# crown-B.net
KiCad netlist of a schematic drawn in EAGLE
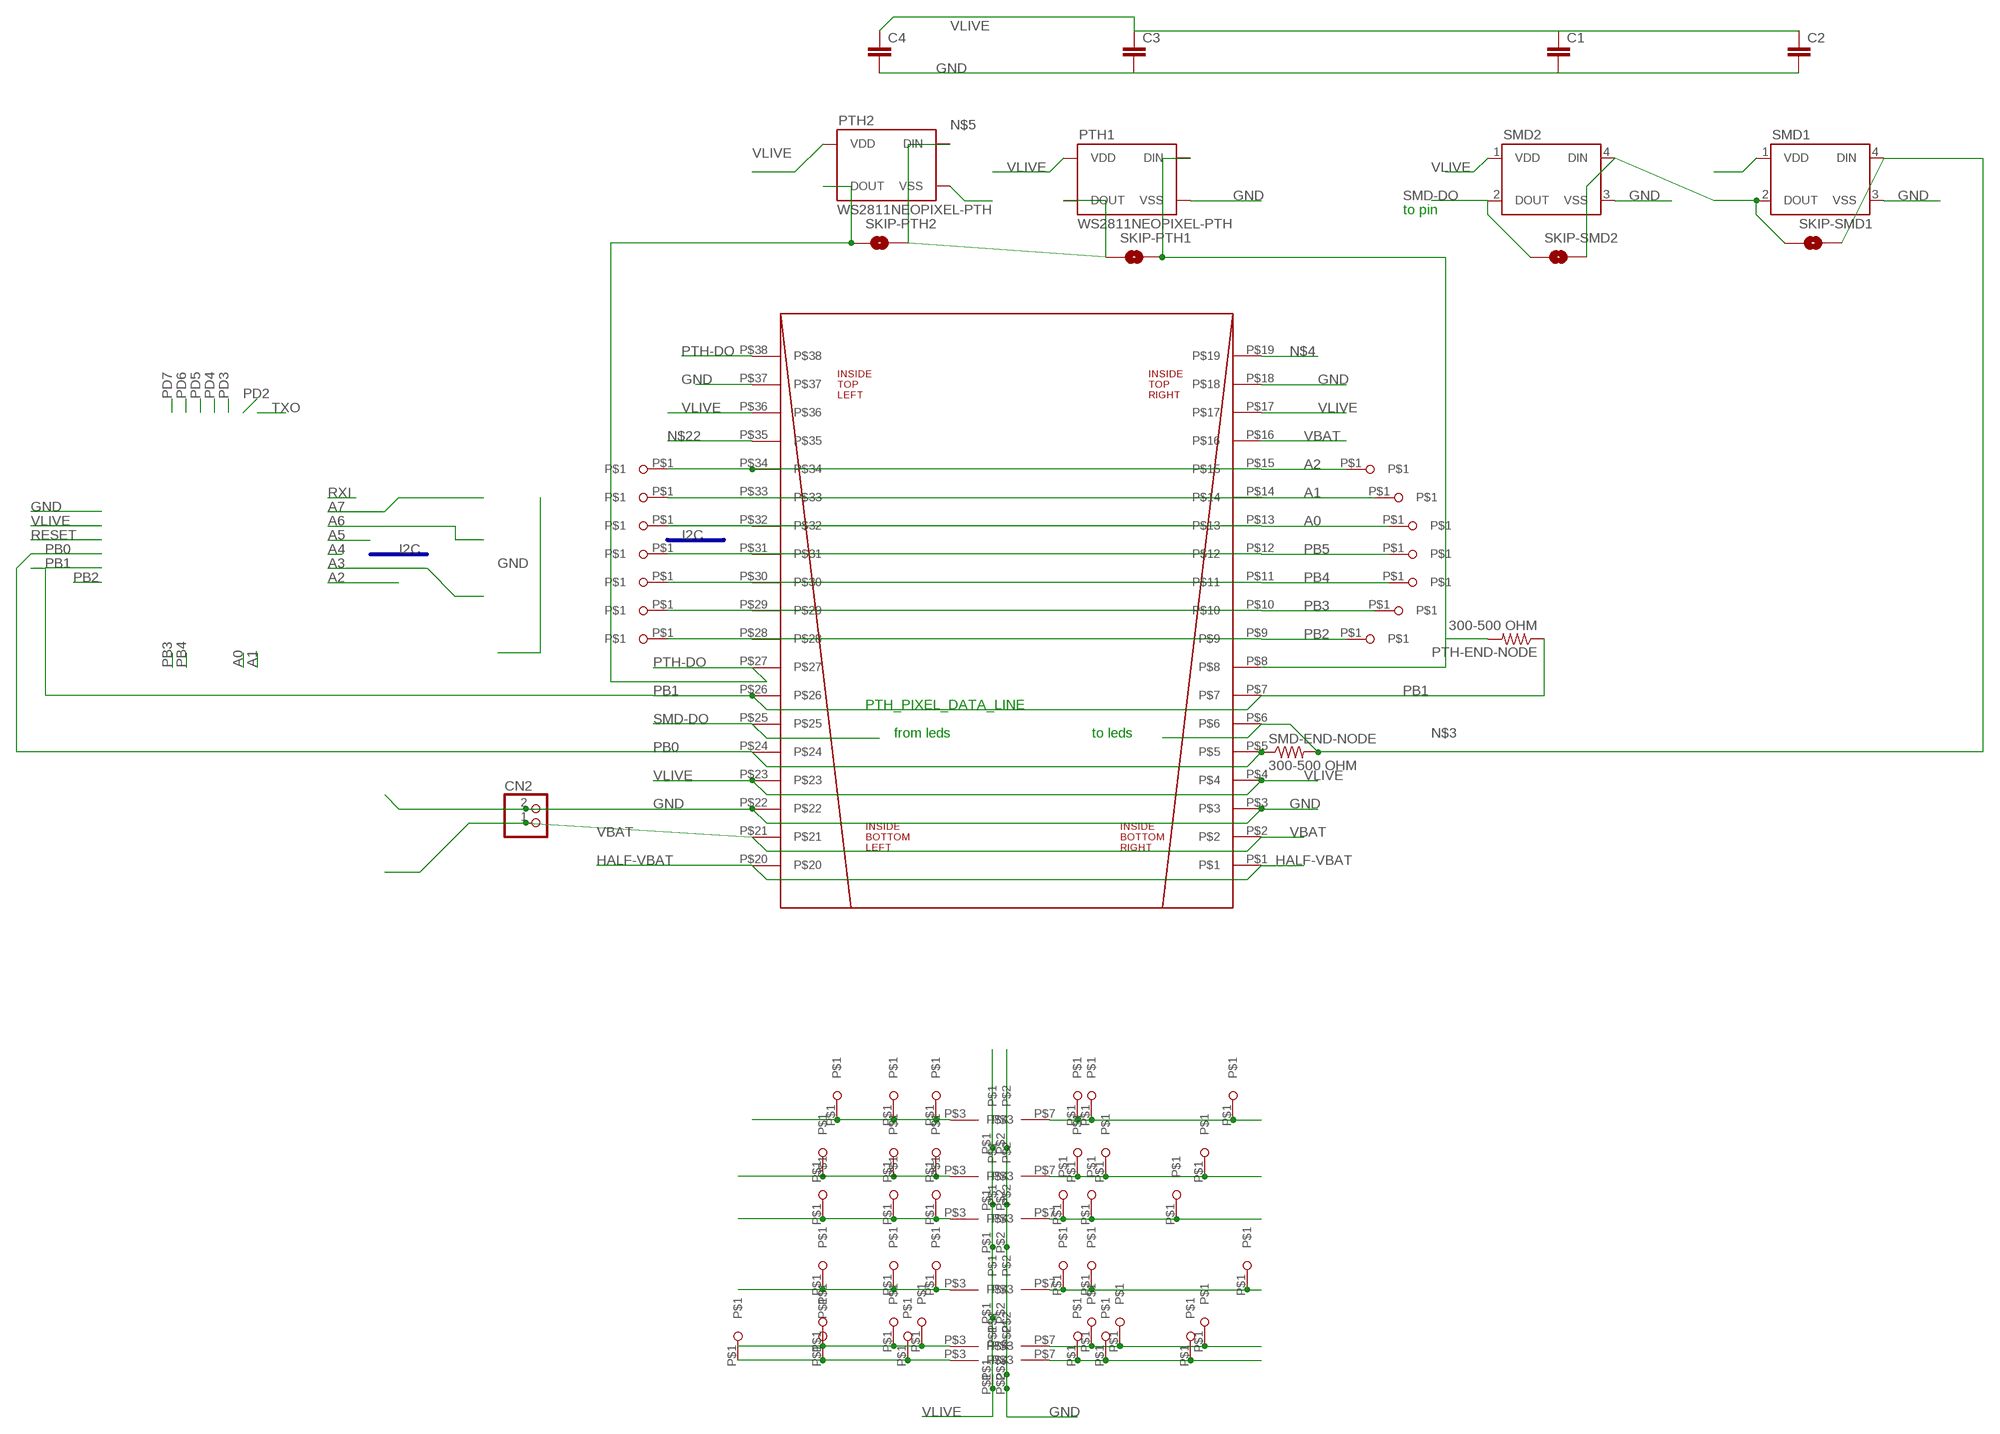
[diagram p0: schematic, sheet 1]

(export (version "E")
  (design (tool "Eeschema 10.0.6"))
  (components
    (comp (ref "C1")
      (value "CAP0805")
      (footprint "eagle-import:0805")
      (libsource (lib "eagle-import") (part "CAP0805"))
    )
    (comp (ref "C2")
      (value "CAP0805")
      (footprint "eagle-import:0805")
      (libsource (lib "eagle-import") (part "CAP0805"))
    )
    (comp (ref "C3")
      (value "CAP0805")
      (footprint "eagle-import:0805")
      (libsource (lib "eagle-import") (part "CAP0805"))
    )
    (comp (ref "C4")
      (value "CAP0805")
      (footprint "eagle-import:0805")
      (libsource (lib "eagle-import") (part "CAP0805"))
    )
    (comp (ref "CN2")
      (value "JST_2PIN-SMT-RA")
      (footprint "eagle-import:JST-PH-2-SMT-RA")
      (libsource (lib "eagle-import") (part "JST_2PIN-SMT-RA"))
    )
    (comp (ref "PTH-END-NODE")
      (value "300-500 OHM")
      (footprint "eagle-import:0805")
      (libsource (lib "eagle-import") (part "RESISTOR0805-RES"))
    )
    (comp (ref "PTH1")
      (value "WS2811NEOPIXEL-PTH")
      (footprint "eagle-import:WS2811-PTH-FLAT")
      (libsource (lib "eagle-import") (part "WS2811NEOPIXEL-PTH"))
    )
    (comp (ref "PTH2")
      (value "WS2811NEOPIXEL-PTH")
      (footprint "eagle-import:WS2811-PTH-FLAT")
      (libsource (lib "eagle-import") (part "WS2811NEOPIXEL-PTH"))
    )
    (comp (ref "SKIP-PTH1")
      (value "SOLDERJUMPERNC2")
      (footprint "eagle-import:SJ_2S-NOTRACE")
      (libsource (lib "eagle-import") (part "SOLDERJUMPERNC2"))
    )
    (comp (ref "SKIP-PTH2")
      (value "SOLDERJUMPERNC2")
      (footprint "eagle-import:SJ_2S-NOTRACE")
      (libsource (lib "eagle-import") (part "SOLDERJUMPERNC2"))
    )
    (comp (ref "SKIP-SMD1")
      (value "SOLDERJUMPERNC2")
      (footprint "eagle-import:SJ_2S-NOTRACE")
      (libsource (lib "eagle-import") (part "SOLDERJUMPERNC2"))
    )
    (comp (ref "SKIP-SMD2")
      (value "SOLDERJUMPERNC2")
      (footprint "eagle-import:SJ_2S-NOTRACE")
      (libsource (lib "eagle-import") (part "SOLDERJUMPERNC2"))
    )
    (comp (ref "SMD-END-NODE")
      (value "300-500 OHM")
      (footprint "eagle-import:0805")
      (libsource (lib "eagle-import") (part "RESISTOR0805-RES"))
    )
    (comp (ref "SMD1")
      (value "WS2812B")
      (footprint "eagle-import:WS2812B")
      (libsource (lib "eagle-import") (part "WS2812B"))
    )
    (comp (ref "SMD2")
      (value "WS2812B")
      (footprint "eagle-import:WS2812B")
      (libsource (lib "eagle-import") (part "WS2812B"))
    )
    (comp (ref "U$1")
      (value "SMD_BREADBOARD")
      (footprint "eagle-import:SMD_BREADBOARD_4X")
      (libsource (lib "eagle-import") (part "SMD_BREADBOARD"))
    )
    (comp (ref "U$2")
      (value "CROWNSTANDARD")
      (footprint "eagle-import:CROWN")
      (libsource (lib "eagle-import") (part "CROWNSTANDARD"))
    )
    (comp (ref "U$3")
      (value "SMD_BREADBOARD")
      (footprint "eagle-import:SMD_BREADBOARD_4X")
      (libsource (lib "eagle-import") (part "SMD_BREADBOARD"))
    )
    (comp (ref "U$4")
      (value "SMD_BREADBOARD")
      (footprint "eagle-import:SMD_BREADBOARD_4X")
      (libsource (lib "eagle-import") (part "SMD_BREADBOARD"))
    )
    (comp (ref "U$5")
      (value "SMD_BREADBOARD")
      (footprint "eagle-import:SMD_BREADBOARD_4X")
      (libsource (lib "eagle-import") (part "SMD_BREADBOARD"))
    )
    (comp (ref "U$6")
      (value "SMD_BREADBOARD")
      (footprint "eagle-import:SMD_BREADBOARD_4X")
      (libsource (lib "eagle-import") (part "SMD_BREADBOARD"))
    )
    (comp (ref "U$7")
      (value "SMD_BREADBOARD")
      (footprint "eagle-import:SMD_BREADBOARD_4X")
      (libsource (lib "eagle-import") (part "SMD_BREADBOARD"))
    )
    (comp (ref "U$10")
      (value "SMD_PAD")
      (footprint "eagle-import:SMD_BREADBOARD_PAD")
      (libsource (lib "eagle-import") (part "SMD_PAD"))
    )
    (comp (ref "U$11")
      (value "SMD_PAD")
      (footprint "eagle-import:SMD_BREADBOARD_PAD")
      (libsource (lib "eagle-import") (part "SMD_PAD"))
    )
    (comp (ref "U$12")
      (value "SMD_PAD")
      (footprint "eagle-import:SMD_BREADBOARD_PAD")
      (libsource (lib "eagle-import") (part "SMD_PAD"))
    )
    (comp (ref "U$13")
      (value "SMD_PAD")
      (footprint "eagle-import:SMD_BREADBOARD_PAD")
      (libsource (lib "eagle-import") (part "SMD_PAD"))
    )
    (comp (ref "U$14")
      (value "SMD_PAD")
      (footprint "eagle-import:SMD_BREADBOARD_PAD")
      (libsource (lib "eagle-import") (part "SMD_PAD"))
    )
    (comp (ref "U$15")
      (value "SMD_PAD")
      (footprint "eagle-import:SMD_BREADBOARD_PAD")
      (libsource (lib "eagle-import") (part "SMD_PAD"))
    )
    (comp (ref "U$16")
      (value "SMD_PAD")
      (footprint "eagle-import:SMD_BREADBOARD_PAD")
      (libsource (lib "eagle-import") (part "SMD_PAD"))
    )
    (comp (ref "U$17")
      (value "SMD_PAD")
      (footprint "eagle-import:SMD_BREADBOARD_PAD")
      (libsource (lib "eagle-import") (part "SMD_PAD"))
    )
    (comp (ref "U$22")
      (value "SMD_PAD")
      (footprint "eagle-import:SMD_BREADBOARD_PAD")
      (libsource (lib "eagle-import") (part "SMD_PAD"))
    )
    (comp (ref "U$23")
      (value "SMD_PAD")
      (footprint "eagle-import:SMD_BREADBOARD_PAD")
      (libsource (lib "eagle-import") (part "SMD_PAD"))
    )
    (comp (ref "U$24")
      (value "SMD_PAD")
      (footprint "eagle-import:SMD_BREADBOARD_PAD")
      (libsource (lib "eagle-import") (part "SMD_PAD"))
    )
    (comp (ref "U$25")
      (value "SMD_PAD")
      (footprint "eagle-import:SMD_BREADBOARD_PAD")
      (libsource (lib "eagle-import") (part "SMD_PAD"))
    )
    (comp (ref "U$26")
      (value "SMD_PAD")
      (footprint "eagle-import:SMD_BREADBOARD_PAD")
      (libsource (lib "eagle-import") (part "SMD_PAD"))
    )
    (comp (ref "U$27")
      (value "SMD_PAD")
      (footprint "eagle-import:SMD_BREADBOARD_PAD")
      (libsource (lib "eagle-import") (part "SMD_PAD"))
    )
    (comp (ref "U$28")
      (value "SMD_PAD")
      (footprint "eagle-import:SMD_BREADBOARD_PAD")
      (libsource (lib "eagle-import") (part "SMD_PAD"))
    )
    (comp (ref "U$29")
      (value "SMD_PAD")
      (footprint "eagle-import:SMD_BREADBOARD_PAD")
      (libsource (lib "eagle-import") (part "SMD_PAD"))
    )
    (comp (ref "U$34")
      (value "SMD_PAD")
      (footprint "eagle-import:SMD_BREADBOARD_PAD")
      (libsource (lib "eagle-import") (part "SMD_PAD"))
    )
    (comp (ref "U$35")
      (value "SMD_PAD")
      (footprint "eagle-import:SMD_BREADBOARD_PAD")
      (libsource (lib "eagle-import") (part "SMD_PAD"))
    )
    (comp (ref "U$36")
      (value "SMD_PAD")
      (footprint "eagle-import:SMD_BREADBOARD_PAD")
      (libsource (lib "eagle-import") (part "SMD_PAD"))
    )
    (comp (ref "U$37")
      (value "SMD_PAD")
      (footprint "eagle-import:SMD_BREADBOARD_PAD")
      (libsource (lib "eagle-import") (part "SMD_PAD"))
    )
    (comp (ref "U$38")
      (value "SMD_PAD")
      (footprint "eagle-import:SMD_BREADBOARD_PAD")
      (libsource (lib "eagle-import") (part "SMD_PAD"))
    )
    (comp (ref "U$39")
      (value "SMD_PAD")
      (footprint "eagle-import:SMD_BREADBOARD_PAD")
      (libsource (lib "eagle-import") (part "SMD_PAD"))
    )
    (comp (ref "U$40")
      (value "SMD_PAD")
      (footprint "eagle-import:SMD_BREADBOARD_PAD")
      (libsource (lib "eagle-import") (part "SMD_PAD"))
    )
    (comp (ref "U$41")
      (value "SMD_PAD")
      (footprint "eagle-import:SMD_BREADBOARD_PAD")
      (libsource (lib "eagle-import") (part "SMD_PAD"))
    )
    (comp (ref "U$42")
      (value "SMD_PAD")
      (footprint "eagle-import:SMD_BREADBOARD_PAD")
      (libsource (lib "eagle-import") (part "SMD_PAD"))
    )
    (comp (ref "U$43")
      (value "SMD_PAD")
      (footprint "eagle-import:SMD_BREADBOARD_PAD")
      (libsource (lib "eagle-import") (part "SMD_PAD"))
    )
    (comp (ref "U$44")
      (value "SMD_PAD")
      (footprint "eagle-import:SMD_BREADBOARD_PAD")
      (libsource (lib "eagle-import") (part "SMD_PAD"))
    )
    (comp (ref "U$45")
      (value "SMD_PAD")
      (footprint "eagle-import:SMD_BREADBOARD_PAD")
      (libsource (lib "eagle-import") (part "SMD_PAD"))
    )
    (comp (ref "U$46")
      (value "SMD_PAD")
      (footprint "eagle-import:SMD_BREADBOARD_PAD")
      (libsource (lib "eagle-import") (part "SMD_PAD"))
    )
    (comp (ref "U$47")
      (value "SMD_PAD")
      (footprint "eagle-import:SMD_BREADBOARD_PAD")
      (libsource (lib "eagle-import") (part "SMD_PAD"))
    )
    (comp (ref "U$48")
      (value "SMD_PAD")
      (footprint "eagle-import:SMD_BREADBOARD_PAD")
      (libsource (lib "eagle-import") (part "SMD_PAD"))
    )
    (comp (ref "U$49")
      (value "SMD_PAD")
      (footprint "eagle-import:SMD_BREADBOARD_PAD")
      (libsource (lib "eagle-import") (part "SMD_PAD"))
    )
    (comp (ref "U$50")
      (value "SMD_PAD")
      (footprint "eagle-import:SMD_BREADBOARD_PAD")
      (libsource (lib "eagle-import") (part "SMD_PAD"))
    )
    (comp (ref "U$51")
      (value "SMD_PAD")
      (footprint "eagle-import:SMD_BREADBOARD_PAD")
      (libsource (lib "eagle-import") (part "SMD_PAD"))
    )
    (comp (ref "U$52")
      (value "SMD_PAD")
      (footprint "eagle-import:SMD_BREADBOARD_PAD")
      (libsource (lib "eagle-import") (part "SMD_PAD"))
    )
    (comp (ref "U$53")
      (value "SMD_PAD")
      (footprint "eagle-import:SMD_BREADBOARD_PAD")
      (libsource (lib "eagle-import") (part "SMD_PAD"))
    )
    (comp (ref "U$54")
      (value "SMD_PAD")
      (footprint "eagle-import:SMD_BREADBOARD_PAD")
      (libsource (lib "eagle-import") (part "SMD_PAD"))
    )
    (comp (ref "U$55")
      (value "SMD_PAD")
      (footprint "eagle-import:SMD_BREADBOARD_PAD")
      (libsource (lib "eagle-import") (part "SMD_PAD"))
    )
    (comp (ref "U$56")
      (value "SMD_PAD")
      (footprint "eagle-import:SMD_BREADBOARD_PAD")
      (libsource (lib "eagle-import") (part "SMD_PAD"))
    )
    (comp (ref "U$57")
      (value "SMD_PAD")
      (footprint "eagle-import:SMD_BREADBOARD_PAD")
      (libsource (lib "eagle-import") (part "SMD_PAD"))
    )
    (comp (ref "U$58")
      (value "SMD_PAD")
      (footprint "eagle-import:SMD_BREADBOARD_PAD")
      (libsource (lib "eagle-import") (part "SMD_PAD"))
    )
    (comp (ref "U$59")
      (value "SMD_PAD")
      (footprint "eagle-import:SMD_BREADBOARD_PAD")
      (libsource (lib "eagle-import") (part "SMD_PAD"))
    )
    (comp (ref "U$62")
      (value "SMD_PAD")
      (footprint "eagle-import:SMD_BREADBOARD_PAD")
      (libsource (lib "eagle-import") (part "SMD_PAD"))
    )
    (comp (ref "U$63")
      (value "SMD_PAD")
      (footprint "eagle-import:SMD_BREADBOARD_PAD")
      (libsource (lib "eagle-import") (part "SMD_PAD"))
    )
    (comp (ref "U$64")
      (value "SMD_PAD")
      (footprint "eagle-import:SMD_BREADBOARD_PAD")
      (libsource (lib "eagle-import") (part "SMD_PAD"))
    )
    (comp (ref "U$65")
      (value "SMD_PAD")
      (footprint "eagle-import:SMD_BREADBOARD_PAD")
      (libsource (lib "eagle-import") (part "SMD_PAD"))
    )
    (comp (ref "U$68")
      (value "SMD_PAD")
      (footprint "eagle-import:SMD_BREADBOARD_PAD")
      (libsource (lib "eagle-import") (part "SMD_PAD"))
    )
    (comp (ref "U$69")
      (value "SMD_PAD")
      (footprint "eagle-import:SMD_BREADBOARD_PAD")
      (libsource (lib "eagle-import") (part "SMD_PAD"))
    )
    (comp (ref "U$70")
      (value "SMD_PAD")
      (footprint "eagle-import:SMD_BREADBOARD_PAD")
      (libsource (lib "eagle-import") (part "SMD_PAD"))
    )
    (comp (ref "U$71")
      (value "SMD_PAD")
      (footprint "eagle-import:SMD_BREADBOARD_PAD")
      (libsource (lib "eagle-import") (part "SMD_PAD"))
    )
  )
  (nets
    (net (code "2") (name "/A0") (class "Default")
      (node (ref "U$2") (pin "P$13") (pinfunction "P$13_P$13") (pintype "bidirectional"))
      (node (ref "U$2") (pin "P$32") (pinfunction "P$32_P$32") (pintype "bidirectional"))
      (node (ref "U$44") (pin "P$1") (pinfunction "P$1_P$1") (pintype "bidirectional"))
      (node (ref "U$55") (pin "P$1") (pinfunction "P$1_P$1") (pintype "bidirectional"))
    )
    (net (code "3") (name "/A1") (class "Default")
      (node (ref "U$2") (pin "P$14") (pinfunction "P$14_P$14") (pintype "bidirectional"))
      (node (ref "U$2") (pin "P$33") (pinfunction "P$33_P$33") (pintype "bidirectional"))
      (node (ref "U$43") (pin "P$1") (pinfunction "P$1_P$1") (pintype "bidirectional"))
      (node (ref "U$56") (pin "P$1") (pinfunction "P$1_P$1") (pintype "bidirectional"))
    )
    (net (code "4") (name "/A2") (class "Default")
      (node (ref "U$2") (pin "P$15") (pinfunction "P$15_P$15") (pintype "bidirectional"))
      (node (ref "U$2") (pin "P$34") (pinfunction "P$34_P$34") (pintype "bidirectional"))
      (node (ref "U$42") (pin "P$1") (pinfunction "P$1_P$1") (pintype "bidirectional"))
      (node (ref "U$58") (pin "P$1") (pinfunction "P$1_P$1") (pintype "bidirectional"))
    )
    (net (code "10") (name "/GND") (class "Default")
      (node (ref "C1") (pin "2") (pinfunction "2_2") (pintype "passive"))
      (node (ref "C2") (pin "2") (pinfunction "2_2") (pintype "passive"))
      (node (ref "C3") (pin "2") (pinfunction "2_2") (pintype "passive"))
      (node (ref "C4") (pin "2") (pinfunction "2_2") (pintype "passive"))
      (node (ref "CN2") (pin "2") (pinfunction "1_2") (pintype "passive"))
      (node (ref "PTH1") (pin "P$2") (pinfunction "VSS_P$2") (pintype "power_in"))
      (node (ref "PTH1") (pin "P$6") (pinfunction "VSS_P$6") (pintype "power_in"))
      (node (ref "PTH2") (pin "P$2") (pinfunction "VSS_P$2") (pintype "power_in"))
      (node (ref "PTH2") (pin "P$6") (pinfunction "VSS_P$6") (pintype "power_in"))
      (node (ref "SMD1") (pin "3") (pinfunction "VSS_3") (pintype "power_in"))
      (node (ref "SMD2") (pin "3") (pinfunction "VSS_3") (pintype "power_in"))
      (node (ref "U$1") (pin "P$2") (pinfunction "P$2_P$2") (pintype "bidirectional"))
      (node (ref "U$2") (pin "P$18") (pinfunction "P$18_P$18") (pintype "bidirectional"))
      (node (ref "U$2") (pin "P$22") (pinfunction "P$22_P$22") (pintype "bidirectional"))
      (node (ref "U$2") (pin "P$3") (pinfunction "P$3_P$3") (pintype "bidirectional"))
      (node (ref "U$2") (pin "P$37") (pinfunction "P$37_P$37") (pintype "bidirectional"))
      (node (ref "U$3") (pin "P$2") (pinfunction "P$2_P$2") (pintype "bidirectional"))
      (node (ref "U$4") (pin "P$2") (pinfunction "P$2_P$2") (pintype "bidirectional"))
      (node (ref "U$5") (pin "P$2") (pinfunction "P$2_P$2") (pintype "bidirectional"))
      (node (ref "U$6") (pin "P$2") (pinfunction "P$2_P$2") (pintype "bidirectional"))
      (node (ref "U$7") (pin "P$2") (pinfunction "P$2_P$2") (pintype "bidirectional"))
    )
    (net (code "11") (name "/HALF-VBAT") (class "Default")
      (node (ref "U$2") (pin "P$1") (pinfunction "P$1_P$1") (pintype "bidirectional"))
      (node (ref "U$2") (pin "P$20") (pinfunction "P$20_P$20") (pintype "bidirectional"))
    )
    (net (code "12") (name "/N$3") (class "Default")
      (node (ref "SKIP-SMD1") (pin "2") (pinfunction "2_2") (pintype "passive"))
      (node (ref "SMD-END-NODE") (pin "2") (pinfunction "2_2") (pintype "passive"))
      (node (ref "SMD1") (pin "4") (pinfunction "DIN_4") (pintype "input"))
      (node (ref "U$2") (pin "P$6") (pinfunction "P$6_P$6") (pintype "bidirectional"))
    )
    (net (code "13") (name "/N$4") (class "Default")
      (node (ref "PTH-END-NODE") (pin "2") (pinfunction "2_2") (pintype "passive"))
      (node (ref "PTH1") (pin "P$4") (pinfunction "DIN_P$4") (pintype "input"))
      (node (ref "PTH1") (pin "P$8") (pinfunction "DIN_P$8") (pintype "input"))
      (node (ref "SKIP-PTH1") (pin "2") (pinfunction "2_2") (pintype "passive"))
      (node (ref "U$2") (pin "P$19") (pinfunction "P$19_P$19") (pintype "bidirectional"))
      (node (ref "U$2") (pin "P$8") (pinfunction "P$8_P$8") (pintype "bidirectional"))
    )
    (net (code "14") (name "/N$5") (class "Default")
      (node (ref "PTH1") (pin "P$1") (pinfunction "DOUT_P$1") (pintype "output"))
      (node (ref "PTH1") (pin "P$5") (pinfunction "DOUT_P$5") (pintype "output"))
      (node (ref "PTH2") (pin "P$4") (pinfunction "DIN_P$4") (pintype "input"))
      (node (ref "PTH2") (pin "P$8") (pinfunction "DIN_P$8") (pintype "input"))
      (node (ref "SKIP-PTH1") (pin "1") (pinfunction "1_1") (pintype "passive"))
      (node (ref "SKIP-PTH2") (pin "2") (pinfunction "2_2") (pintype "passive"))
    )
    (net (code "15") (name "/N$22") (class "Default")
      (node (ref "U$2") (pin "P$35") (pinfunction "P$35_P$35") (pintype "bidirectional"))
    )
    (net (code "16") (name "/PB0") (class "Default")
      (node (ref "SMD-END-NODE") (pin "1") (pinfunction "1_1") (pintype "passive"))
      (node (ref "U$2") (pin "P$24") (pinfunction "P$24_P$24") (pintype "bidirectional"))
      (node (ref "U$2") (pin "P$5") (pinfunction "P$5_P$5") (pintype "bidirectional"))
    )
    (net (code "17") (name "/PB1") (class "Default")
      (node (ref "PTH-END-NODE") (pin "1") (pinfunction "1_1") (pintype "passive"))
      (node (ref "U$2") (pin "P$26") (pinfunction "P$26_P$26") (pintype "bidirectional"))
      (node (ref "U$2") (pin "P$7") (pinfunction "P$7_P$7") (pintype "bidirectional"))
    )
    (net (code "18") (name "/PB2") (class "Default")
      (node (ref "U$2") (pin "P$28") (pinfunction "P$28_P$28") (pintype "bidirectional"))
      (node (ref "U$2") (pin "P$9") (pinfunction "P$9_P$9") (pintype "bidirectional"))
      (node (ref "U$48") (pin "P$1") (pinfunction "P$1_P$1") (pintype "bidirectional"))
      (node (ref "U$51") (pin "P$1") (pinfunction "P$1_P$1") (pintype "bidirectional"))
    )
    (net (code "19") (name "/PB3") (class "Default")
      (node (ref "U$2") (pin "P$10") (pinfunction "P$10_P$10") (pintype "bidirectional"))
      (node (ref "U$2") (pin "P$29") (pinfunction "P$29_P$29") (pintype "bidirectional"))
      (node (ref "U$47") (pin "P$1") (pinfunction "P$1_P$1") (pintype "bidirectional"))
      (node (ref "U$52") (pin "P$1") (pinfunction "P$1_P$1") (pintype "bidirectional"))
    )
    (net (code "20") (name "/PB4") (class "Default")
      (node (ref "U$2") (pin "P$11") (pinfunction "P$11_P$11") (pintype "bidirectional"))
      (node (ref "U$2") (pin "P$30") (pinfunction "P$30_P$30") (pintype "bidirectional"))
      (node (ref "U$46") (pin "P$1") (pinfunction "P$1_P$1") (pintype "bidirectional"))
      (node (ref "U$53") (pin "P$1") (pinfunction "P$1_P$1") (pintype "bidirectional"))
    )
    (net (code "21") (name "/PB5") (class "Default")
      (node (ref "U$2") (pin "P$12") (pinfunction "P$12_P$12") (pintype "bidirectional"))
      (node (ref "U$2") (pin "P$31") (pinfunction "P$31_P$31") (pintype "bidirectional"))
      (node (ref "U$45") (pin "P$1") (pinfunction "P$1_P$1") (pintype "bidirectional"))
      (node (ref "U$54") (pin "P$1") (pinfunction "P$1_P$1") (pintype "bidirectional"))
    )
    (net (code "28") (name "/PTH-DO") (class "Default")
      (node (ref "PTH2") (pin "P$1") (pinfunction "DOUT_P$1") (pintype "output"))
      (node (ref "PTH2") (pin "P$5") (pinfunction "DOUT_P$5") (pintype "output"))
      (node (ref "SKIP-PTH2") (pin "1") (pinfunction "1_1") (pintype "passive"))
      (node (ref "U$2") (pin "P$27") (pinfunction "P$27_P$27") (pintype "bidirectional"))
      (node (ref "U$2") (pin "P$38") (pinfunction "P$38_P$38") (pintype "bidirectional"))
    )
    (net (code "31") (name "/SMD-DO") (class "Default")
      (node (ref "SKIP-SMD2") (pin "1") (pinfunction "1_1") (pintype "passive"))
      (node (ref "SMD2") (pin "2") (pinfunction "DOUT_2") (pintype "output"))
      (node (ref "U$2") (pin "P$25") (pinfunction "P$25_P$25") (pintype "bidirectional"))
    )
    (net (code "33") (name "/VBAT") (class "Default")
      (node (ref "CN2") (pin "1") (pinfunction "2_1") (pintype "passive"))
      (node (ref "U$2") (pin "P$16") (pinfunction "P$16_P$16") (pintype "bidirectional"))
      (node (ref "U$2") (pin "P$2") (pinfunction "P$2_P$2") (pintype "bidirectional"))
      (node (ref "U$2") (pin "P$21") (pinfunction "P$21_P$21") (pintype "bidirectional"))
    )
    (net (code "34") (name "/VLIVE") (class "Default")
      (node (ref "C1") (pin "1") (pinfunction "1_1") (pintype "passive"))
      (node (ref "C2") (pin "1") (pinfunction "1_1") (pintype "passive"))
      (node (ref "C3") (pin "1") (pinfunction "1_1") (pintype "passive"))
      (node (ref "C4") (pin "1") (pinfunction "1_1") (pintype "passive"))
      (node (ref "PTH1") (pin "P$3") (pinfunction "VDD_P$3") (pintype "power_in"))
      (node (ref "PTH1") (pin "P$7") (pinfunction "VDD_P$7") (pintype "power_in"))
      (node (ref "PTH2") (pin "P$3") (pinfunction "VDD_P$3") (pintype "power_in"))
      (node (ref "PTH2") (pin "P$7") (pinfunction "VDD_P$7") (pintype "power_in"))
      (node (ref "SMD1") (pin "1") (pinfunction "VDD_1") (pintype "power_in"))
      (node (ref "SMD2") (pin "1") (pinfunction "VDD_1") (pintype "power_in"))
      (node (ref "U$1") (pin "P$1") (pinfunction "P$1_P$1") (pintype "bidirectional"))
      (node (ref "U$2") (pin "P$17") (pinfunction "P$17_P$17") (pintype "bidirectional"))
      (node (ref "U$2") (pin "P$23") (pinfunction "P$23_P$23") (pintype "bidirectional"))
      (node (ref "U$2") (pin "P$36") (pinfunction "P$36_P$36") (pintype "bidirectional"))
      (node (ref "U$2") (pin "P$4") (pinfunction "P$4_P$4") (pintype "bidirectional"))
      (node (ref "U$3") (pin "P$1") (pinfunction "P$1_P$1") (pintype "bidirectional"))
      (node (ref "U$4") (pin "P$1") (pinfunction "P$1_P$1") (pintype "bidirectional"))
      (node (ref "U$5") (pin "P$1") (pinfunction "P$1_P$1") (pintype "bidirectional"))
      (node (ref "U$6") (pin "P$1") (pinfunction "P$1_P$1") (pintype "bidirectional"))
      (node (ref "U$7") (pin "P$1") (pinfunction "P$1_P$1") (pintype "bidirectional"))
    )
    (net (code "36") (name "Net-(SMD1-DOUT)") (class "Default")
      (node (ref "SKIP-SMD1") (pin "1") (pinfunction "1_1") (pintype "passive"))
      (node (ref "SKIP-SMD2") (pin "2") (pinfunction "2_2") (pintype "passive"))
      (node (ref "SMD1") (pin "2") (pinfunction "DOUT_2") (pintype "output"))
      (node (ref "SMD2") (pin "4") (pinfunction "DIN_4") (pintype "input"))
    )
    (net (code "37") (name "Net-(U$1-P$4)") (class "Default")
      (node (ref "U$1") (pin "P$7") (pinfunction "P$4_P$7") (pintype "bidirectional"))
      (node (ref "U$26") (pin "P$1") (pinfunction "P$1_P$1") (pintype "bidirectional"))
      (node (ref "U$27") (pin "P$1") (pinfunction "P$1_P$1") (pintype "bidirectional"))
      (node (ref "U$64") (pin "P$1") (pinfunction "P$1_P$1") (pintype "bidirectional"))
    )
    (net (code "38") (name "Net-(U$1-PadP$3)") (class "Default")
      (node (ref "U$1") (pin "P$3") (pinfunction "P$3_P$3") (pintype "bidirectional"))
      (node (ref "U$24") (pin "P$1") (pinfunction "P$1_P$1") (pintype "bidirectional"))
      (node (ref "U$25") (pin "P$1") (pinfunction "P$1_P$1") (pintype "bidirectional"))
      (node (ref "U$63") (pin "P$1") (pinfunction "P$1_P$1") (pintype "bidirectional"))
    )
    (net (code "39") (name "Net-(U$3-P$4)") (class "Default")
      (node (ref "U$28") (pin "P$1") (pinfunction "P$1_P$1") (pintype "bidirectional"))
      (node (ref "U$29") (pin "P$1") (pinfunction "P$1_P$1") (pintype "bidirectional"))
      (node (ref "U$3") (pin "P$7") (pinfunction "P$4_P$7") (pintype "bidirectional"))
      (node (ref "U$65") (pin "P$1") (pinfunction "P$1_P$1") (pintype "bidirectional"))
    )
    (net (code "40") (name "Net-(U$4-P$4)") (class "Default")
      (node (ref "U$34") (pin "P$1") (pinfunction "P$1_P$1") (pintype "bidirectional"))
      (node (ref "U$35") (pin "P$1") (pinfunction "P$1_P$1") (pintype "bidirectional"))
      (node (ref "U$4") (pin "P$7") (pinfunction "P$4_P$7") (pintype "bidirectional"))
      (node (ref "U$68") (pin "P$1") (pinfunction "P$1_P$1") (pintype "bidirectional"))
    )
    (net (code "41") (name "Net-(U$5-P$4)") (class "Default")
      (node (ref "U$36") (pin "P$1") (pinfunction "P$1_P$1") (pintype "bidirectional"))
      (node (ref "U$37") (pin "P$1") (pinfunction "P$1_P$1") (pintype "bidirectional"))
      (node (ref "U$5") (pin "P$7") (pinfunction "P$4_P$7") (pintype "bidirectional"))
      (node (ref "U$69") (pin "P$1") (pinfunction "P$1_P$1") (pintype "bidirectional"))
    )
    (net (code "42") (name "Net-(U$6-P$4)") (class "Default")
      (node (ref "U$38") (pin "P$1") (pinfunction "P$1_P$1") (pintype "bidirectional"))
      (node (ref "U$39") (pin "P$1") (pinfunction "P$1_P$1") (pintype "bidirectional"))
      (node (ref "U$6") (pin "P$7") (pinfunction "P$4_P$7") (pintype "bidirectional"))
      (node (ref "U$70") (pin "P$1") (pinfunction "P$1_P$1") (pintype "bidirectional"))
    )
    (net (code "43") (name "Net-(U$7-P$4)") (class "Default")
      (node (ref "U$40") (pin "P$1") (pinfunction "P$1_P$1") (pintype "bidirectional"))
      (node (ref "U$41") (pin "P$1") (pinfunction "P$1_P$1") (pintype "bidirectional"))
      (node (ref "U$7") (pin "P$7") (pinfunction "P$4_P$7") (pintype "bidirectional"))
      (node (ref "U$71") (pin "P$1") (pinfunction "P$1_P$1") (pintype "bidirectional"))
    )
    (net (code "44") (name "Net-(U$10-PadP$1)") (class "Default")
      (node (ref "U$10") (pin "P$1") (pinfunction "P$1_P$1") (pintype "bidirectional"))
      (node (ref "U$11") (pin "P$1") (pinfunction "P$1_P$1") (pintype "bidirectional"))
      (node (ref "U$49") (pin "P$1") (pinfunction "P$1_P$1") (pintype "bidirectional"))
      (node (ref "U$7") (pin "P$3") (pinfunction "P$3_P$3") (pintype "bidirectional"))
    )
    (net (code "45") (name "Net-(U$12-PadP$1)") (class "Default")
      (node (ref "U$12") (pin "P$1") (pinfunction "P$1_P$1") (pintype "bidirectional"))
      (node (ref "U$13") (pin "P$1") (pinfunction "P$1_P$1") (pintype "bidirectional"))
      (node (ref "U$50") (pin "P$1") (pinfunction "P$1_P$1") (pintype "bidirectional"))
      (node (ref "U$6") (pin "P$3") (pinfunction "P$3_P$3") (pintype "bidirectional"))
    )
    (net (code "46") (name "Net-(U$14-PadP$1)") (class "Default")
      (node (ref "U$14") (pin "P$1") (pinfunction "P$1_P$1") (pintype "bidirectional"))
      (node (ref "U$15") (pin "P$1") (pinfunction "P$1_P$1") (pintype "bidirectional"))
      (node (ref "U$5") (pin "P$3") (pinfunction "P$3_P$3") (pintype "bidirectional"))
      (node (ref "U$57") (pin "P$1") (pinfunction "P$1_P$1") (pintype "bidirectional"))
    )
    (net (code "47") (name "Net-(U$16-PadP$1)") (class "Default")
      (node (ref "U$16") (pin "P$1") (pinfunction "P$1_P$1") (pintype "bidirectional"))
      (node (ref "U$17") (pin "P$1") (pinfunction "P$1_P$1") (pintype "bidirectional"))
      (node (ref "U$4") (pin "P$3") (pinfunction "P$3_P$3") (pintype "bidirectional"))
      (node (ref "U$59") (pin "P$1") (pinfunction "P$1_P$1") (pintype "bidirectional"))
    )
    (net (code "48") (name "Net-(U$22-PadP$1)") (class "Default")
      (node (ref "U$22") (pin "P$1") (pinfunction "P$1_P$1") (pintype "bidirectional"))
      (node (ref "U$23") (pin "P$1") (pinfunction "P$1_P$1") (pintype "bidirectional"))
      (node (ref "U$3") (pin "P$3") (pinfunction "P$3_P$3") (pintype "bidirectional"))
      (node (ref "U$62") (pin "P$1") (pinfunction "P$1_P$1") (pintype "bidirectional"))
    )
  )
)
